# ProPrj_ZXD-BLE-Core_2025-01-08.net
KiCad netlist of a schematic drawn in EasyEDA Pro
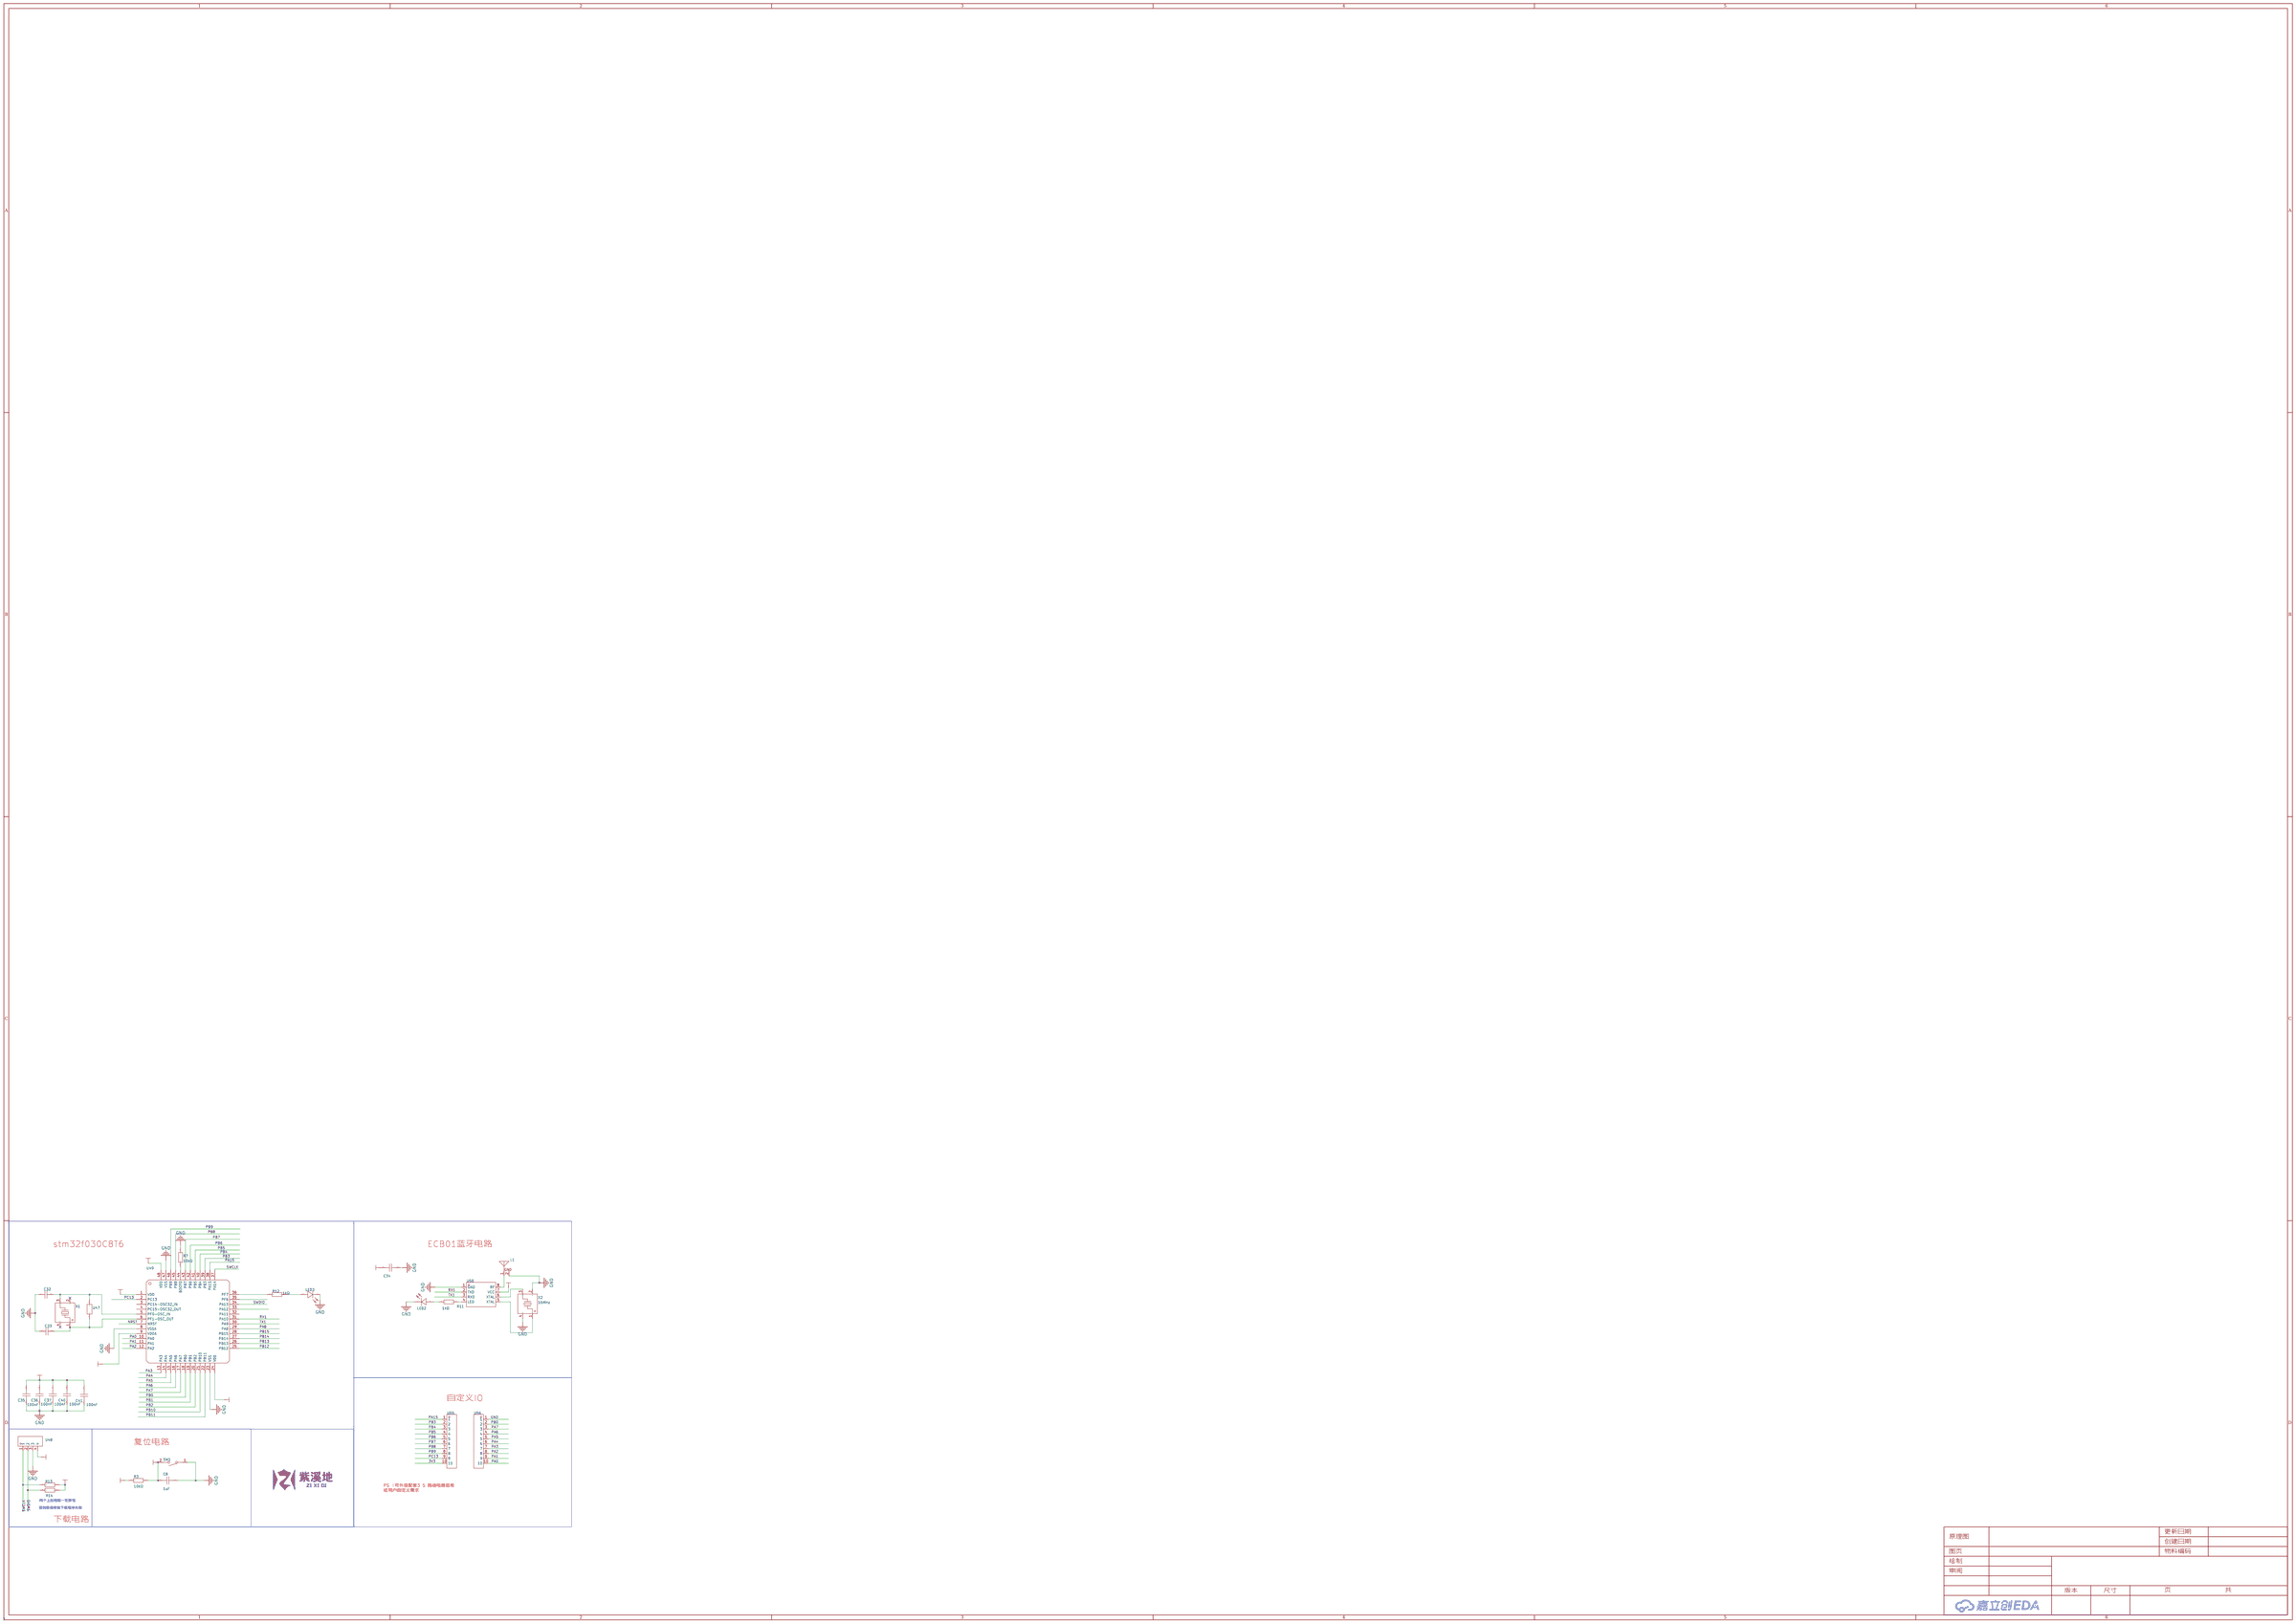
[diagram p0: schematic sheet]

(export (version "E")
  (design (tool "Eeschema 10.0.6"))
  (components
    (comp (ref "C8")
      (value "1uF")
      (fields
        (field (name "Manufacturer Part") "CL10A105KB8NNNC")
        (field (name "Manufacturer") "SAMSUNG(三星)")
      )
      (libsource (lib "easyedapro") (part "CC0603MRX5R8BB106"))
    )
    (comp (ref "C32")
      (value "22pF")
      (footprint "easyedapro:C0603")
      (description "容值:22pF;精度:±5%;额定电压:50V;材质(温度系数):C0G;")
      (fields
        (field (name "Manufacturer Part") "CL10C220JB8NNNC")
        (field (name "Manufacturer") "SAMSUNG(三星)")
      )
      (libsource (lib "easyedapro") (part "CL10C220JB8NNNC"))
    )
    (comp (ref "C33")
      (value "22pF")
      (footprint "easyedapro:C0603")
      (description "容值:22pF;精度:±5%;额定电压:50V;材质(温度系数):C0G;")
      (fields
        (field (name "Manufacturer Part") "CL10C220JB8NNNC")
        (field (name "Manufacturer") "SAMSUNG(三星)")
      )
      (libsource (lib "easyedapro") (part "CL10C220JB8NNNC"))
    )
    (comp (ref "C34")
      (value "100nF")
      (footprint "easyedapro:C0603")
      (description "容值:100nF;精度:±10%;额定电压:50V;材质(温度系数):X7R;")
      (fields
        (field (name "Manufacturer Part") "CGA0603X7R104K500JT")
        (field (name "Manufacturer") "HRE(芯声)")
      )
      (libsource (lib "easyedapro") (part "cga0603x7r104k500jt"))
    )
    (comp (ref "C35")
      (value "100nF")
      (footprint "easyedapro:C0603")
      (description "容值:100nF;精度:±10%;额定电压:50V;材质(温度系数):X7R;")
      (fields
        (field (name "Manufacturer Part") "CC0603KRX7R9BB104")
        (field (name "Manufacturer") "YAGEO(国巨)")
      )
      (libsource (lib "easyedapro") (part "CC0603KRX7R9BB104"))
    )
    (comp (ref "C36")
      (value "100nF")
      (footprint "easyedapro:C0603")
      (description "容值:100nF;精度:±10%;额定电压:50V;材质(温度系数):X7R;")
      (fields
        (field (name "Manufacturer Part") "CC0603KRX7R9BB104")
        (field (name "Manufacturer") "YAGEO(国巨)")
      )
      (libsource (lib "easyedapro") (part "CC0603KRX7R9BB104"))
    )
    (comp (ref "C37")
      (value "100nF")
      (footprint "easyedapro:C0603")
      (description "容值:100nF;精度:±10%;额定电压:50V;材质(温度系数):X7R;")
      (fields
        (field (name "Manufacturer Part") "CC0603KRX7R9BB104")
        (field (name "Manufacturer") "YAGEO(国巨)")
      )
      (libsource (lib "easyedapro") (part "CC0603KRX7R9BB104"))
    )
    (comp (ref "C40")
      (value "100nF")
      (footprint "easyedapro:C0603")
      (description "容值:100nF;精度:±10%;额定电压:50V;材质(温度系数):X7R;")
      (fields
        (field (name "Manufacturer Part") "CC0603KRX7R9BB104")
        (field (name "Manufacturer") "YAGEO(国巨)")
      )
      (libsource (lib "easyedapro") (part "CC0603KRX7R9BB104"))
    )
    (comp (ref "C41")
      (value "100nF")
      (footprint "easyedapro:C0603")
      (description "容值:100nF;精度:±10%;额定电压:50V;材质(温度系数):X7R;")
      (fields
        (field (name "Manufacturer Part") "CC0603KRX7R9BB104")
        (field (name "Manufacturer") "YAGEO(国巨)")
      )
      (libsource (lib "easyedapro") (part "CC0603KRX7R9BB104"))
    )
    (comp (ref "L1")
      (value "2.4G-ANT")
      (footprint "easyedapro:2.4G-ANT")
      (fields (field (name "Manufacturer Part") "KH3216-A55") (field (name "Manufacturer") "kinghelm(金航标)"))
      (libsource (lib "easyedapro") (part "2.4G-ANT"))
    )
    (comp (ref "LED2")
      (value "KT-0603R")
      (footprint "easyedapro:LED0603-RD")
      (description "发光颜色:红色;功率:-;正向电流:-;主波长:-;二极管配置:-;透镜颜色:-;色温:-;发光角度:-;载带方式:-;工作温度:-40°C~+85°C;")
      (fields (field (name "Manufacturer") "KENTO"))
      (libsource (lib "easyedapro") (part "KT-0603R"))
    )
    (comp (ref "LED3")
      (value "XL-1608UBC-04")
      (footprint "easyedapro:LED0603-RD_BLUE")
      (description "发光颜色:蓝色;功率:80mW;正向电流:25mA;主波长:460nm~469nm;透镜颜色:无色透明透镜;色温:-;发光角度:120°;载带方式:正贴;工作温度:-30°C~+85°C;")
      (fields (field (name "Manufacturer") "XINGLIGHT(成兴光)"))
      (libsource (lib "easyedapro") (part "XL-1608UBC-04"))
    )
    (comp (ref "R3")
      (value "10kΩ")
      (footprint "easyedapro:R0603")
      (description "电阻类型:厚膜电阻;阻值:10kΩ;精度:±1%;功率:100mW;最大工作电压:75V;温度系数:±100ppm/°C;")
      (fields
        (field (name "Manufacturer Part") "0603WAF1002T5E")
        (field (name "Manufacturer") "UNI-ROYAL(厚声)")
      )
      (libsource (lib "easyedapro") (part "0603WAF1002T5E"))
    )
    (comp (ref "R7")
      (value "10kΩ")
      (footprint "easyedapro:R0603")
      (description "电阻类型:厚膜电阻;阻值:10kΩ;精度:±1%;功率:100mW;最大工作电压:75V;温度系数:±100ppm/°C;")
      (fields
        (field (name "Manufacturer Part") "0603WAF1002T5E")
        (field (name "Manufacturer") "UNI-ROYAL(厚声)")
      )
      (libsource (lib "easyedapro") (part "0603WAF1002T5E"))
    )
    (comp (ref "R11")
      (value "1kΩ")
      (footprint "easyedapro:R0603")
      (description "电阻类型:厚膜电阻;阻值:1kΩ;精度:±1%;功率:100mW;最大工作电压:75V;温度系数:±100ppm/°C;")
      (fields
        (field (name "Manufacturer Part") "0603WAF1001T5E")
        (field (name "Manufacturer") "UNI-ROYAL(厚声)")
      )
      (libsource (lib "easyedapro") (part "0603WAF1001T5E"))
    )
    (comp (ref "R12")
      (value "1kΩ")
      (footprint "easyedapro:R0603")
      (description "电阻类型:厚膜电阻;阻值:1kΩ;精度:±1%;功率:100mW;最大工作电压:75V;温度系数:±100ppm/°C;")
      (fields
        (field (name "Manufacturer Part") "0603WAF1001T5E")
        (field (name "Manufacturer") "UNI-ROYAL(厚声)")
      )
      (libsource (lib "easyedapro") (part "0603WAF1001T5E"))
    )
    (comp (ref "R13")
      (value "10kΩ")
      (footprint "easyedapro:R0603")
      (description "电阻类型:厚膜电阻;阻值:10kΩ;精度:±1%;功率:100mW;最大工作电压:75V;温度系数:±100ppm/°C;")
      (fields
        (field (name "Manufacturer Part") "0603WAF1002T5E")
        (field (name "Manufacturer") "UNI-ROYAL(厚声)")
      )
      (libsource (lib "easyedapro") (part "0603WAF1002T5E"))
    )
    (comp (ref "R14")
      (value "10kΩ")
      (footprint "easyedapro:R0603")
      (description "电阻类型:厚膜电阻;阻值:10kΩ;精度:±1%;功率:100mW;最大工作电压:75V;温度系数:±100ppm/°C;")
      (fields
        (field (name "Manufacturer Part") "0603WAF1002T5E")
        (field (name "Manufacturer") "UNI-ROYAL(厚声)")
      )
      (libsource (lib "easyedapro") (part "0603WAF1002T5E"))
    )
    (comp (ref "SW1")
      (value "轻触按键3*4*H")
      (footprint "easyedapro:SW-SMD_L4.0-W2.9-LS5.0")
      (libsource (lib "easyedapro") (part "轻触按键3*4*H"))
    )
    (comp (ref "U47")
      (value "1mΩ")
      (footprint "easyedapro:R0603")
      (description "电阻类型:-;阻值:1mΩ;精度:±1%;功率:100mW;温度系数:±300ppm/°C;")
      (fields
        (field (name "Manufacturer Part") "PA0603FRP070R001L")
        (field (name "Manufacturer") "YAGEO(国巨)")
      )
      (libsource (lib "easyedapro") (part "PA0603FRP070R001L"))
    )
    (comp (ref "U48")
      (value "XH2.54_4P_直插")
      (footprint "easyedapro:CONN-TH_4P-P2.50-XH2.54-4P")
      (libsource (lib "easyedapro") (part "XH2.54_4P_直插"))
    )
    (comp (ref "U49")
      (value "STM32F030C8T6TR")
      (footprint "easyedapro:LQFP-48_L7.0-W7.0-P0.50-LS9.0-BL")
      (description "CPU内核:ARM-M0;程序存储容量:64KB;RAM总容量:8KB;GPIO端口数量:39;工作电压范围:2.4V~3.6V;CPU最大主频:48MHz;程序存储器类型:FLASH;")
      (fields (field (name "Manufacturer") "ST(意法半导体)"))
      (libsource (lib "easyedapro") (part "stm32f030c8t6tr"))
    )
    (comp (ref "U50")
      (value "ECB01C")
      (footprint "easyedapro:SOP-8_L4.9-W3.9-P1.27-LS6.0-BL")
      (libsource (lib "easyedapro") (part "ECB01C"))
    )
    (comp (ref "U55")
      (value "HDGCPH-PZ01-10")
      (footprint "easyedapro:HDR-TH_10P-P2.54-V-M_1")
      (fields (field (name "Manufacturer") "HDGC(华德共创)"))
      (libsource (lib "easyedapro") (part "HDGCPH-PZ01-10"))
    )
    (comp (ref "U56")
      (value "HDGCPH-PZ01-10")
      (footprint "easyedapro:HDR-TH_10P-P2.54-V-M_1")
      (fields (field (name "Manufacturer") "HDGC(华德共创)"))
      (libsource (lib "easyedapro") (part "HDGCPH-PZ01-10"))
    )
    (comp (ref "X1")
      (value "8MHz")
      (footprint "easyedapro:OSC-SMD_4P-L3.2-W2.5-BL")
      (description "晶振类型:贴片晶振;频率:8MHz;常温频差:±10ppm;外接负载电容:12pF;频率稳定度(全温):±20ppm;")
      (fields (field (name "Manufacturer Part") "X32258MOB4SI") (field (name "Manufacturer") "YXC(扬兴晶振)"))
      (libsource (lib "easyedapro") (part "x32258mob4si"))
    )
    (comp (ref "X2")
      (value "16MHz")
      (footprint "easyedapro:CRYSTAL-SMD_4P-L3.2-W2.5-BL-1")
      (description "频率:16MHz;常温频差:±20ppm;外接负载电容:8pF;频率稳定度(全温):±50ppm;")
      (fields
        (field (name "Manufacturer Part") "ABM8AIG-16.000MHZ-82Z-T")
        (field (name "Manufacturer") "ABRACON")
      )
      (libsource (lib "easyedapro") (part "ABM8AIG-16.000MHZ-82Z-T"))
    )
  )
  (nets
    (net (code "1") (name "/PA0") (class "Default")
      (node (ref "U49") (pin "10") (pinfunction "PA0_10") (pintype "unspecified"))
      (node (ref "U56") (pin "10") (pinfunction "10_10") (pintype "unspecified"))
    )
    (net (code "2") (name "/PA1") (class "Default")
      (node (ref "U49") (pin "11") (pinfunction "PA1_11") (pintype "unspecified"))
      (node (ref "U56") (pin "9") (pinfunction "9_9") (pintype "unspecified"))
    )
    (net (code "3") (name "/PA2") (class "Default")
      (node (ref "U49") (pin "12") (pinfunction "PA2_12") (pintype "unspecified"))
      (node (ref "U56") (pin "8") (pinfunction "8_8") (pintype "unspecified"))
    )
    (net (code "4") (name "/PA3") (class "Default")
      (node (ref "U49") (pin "13") (pinfunction "PA3_13") (pintype "unspecified"))
      (node (ref "U56") (pin "7") (pinfunction "7_7") (pintype "unspecified"))
    )
    (net (code "5") (name "/PA4") (class "Default")
      (node (ref "U49") (pin "14") (pinfunction "PA4_14") (pintype "unspecified"))
      (node (ref "U56") (pin "6") (pinfunction "6_6") (pintype "unspecified"))
    )
    (net (code "6") (name "/PA5") (class "Default")
      (node (ref "U49") (pin "15") (pinfunction "PA5_15") (pintype "unspecified"))
      (node (ref "U56") (pin "5") (pinfunction "5_5") (pintype "unspecified"))
    )
    (net (code "7") (name "/PA6") (class "Default")
      (node (ref "U49") (pin "16") (pinfunction "PA6_16") (pintype "unspecified"))
      (node (ref "U56") (pin "4") (pinfunction "4_4") (pintype "unspecified"))
    )
    (net (code "8") (name "/PA7") (class "Default")
      (node (ref "U49") (pin "17") (pinfunction "PA7_17") (pintype "unspecified"))
      (node (ref "U56") (pin "3") (pinfunction "3_3") (pintype "unspecified"))
    )
    (net (code "9") (name "/PA8") (class "Default")
      (node (ref "U49") (pin "29") (pinfunction "PA8_29") (pintype "unspecified"))
    )
    (net (code "10") (name "/PA15") (class "Default")
      (node (ref "U49") (pin "38") (pinfunction "PA15_38") (pintype "unspecified"))
      (node (ref "U55") (pin "1") (pinfunction "1_1") (pintype "unspecified"))
    )
    (net (code "11") (name "/PB0") (class "Default")
      (node (ref "U49") (pin "18") (pinfunction "PB0_18") (pintype "unspecified"))
      (node (ref "U56") (pin "2") (pinfunction "2_2") (pintype "unspecified"))
    )
    (net (code "12") (name "/PB1") (class "Default")
      (node (ref "U49") (pin "19") (pinfunction "PB1_19") (pintype "unspecified"))
    )
    (net (code "13") (name "/PB2") (class "Default")
      (node (ref "U49") (pin "20") (pinfunction "PB2_20") (pintype "unspecified"))
    )
    (net (code "14") (name "/PB3") (class "Default")
      (node (ref "U49") (pin "39") (pinfunction "PB3_39") (pintype "unspecified"))
      (node (ref "U55") (pin "2") (pinfunction "2_2") (pintype "unspecified"))
    )
    (net (code "15") (name "/PB4") (class "Default")
      (node (ref "U49") (pin "40") (pinfunction "PB4_40") (pintype "unspecified"))
      (node (ref "U55") (pin "3") (pinfunction "3_3") (pintype "unspecified"))
    )
    (net (code "16") (name "/PB5") (class "Default")
      (node (ref "U49") (pin "41") (pinfunction "PB5_41") (pintype "unspecified"))
      (node (ref "U55") (pin "4") (pinfunction "4_4") (pintype "unspecified"))
    )
    (net (code "17") (name "/PB6") (class "Default")
      (node (ref "U49") (pin "42") (pinfunction "PB6_42") (pintype "unspecified"))
      (node (ref "U55") (pin "5") (pinfunction "5_5") (pintype "unspecified"))
    )
    (net (code "18") (name "/PB7") (class "Default")
      (node (ref "U49") (pin "43") (pinfunction "PB7_43") (pintype "unspecified"))
      (node (ref "U55") (pin "6") (pinfunction "6_6") (pintype "unspecified"))
    )
    (net (code "19") (name "/PB8") (class "Default")
      (node (ref "U49") (pin "45") (pinfunction "PB8_45") (pintype "unspecified"))
      (node (ref "U55") (pin "7") (pinfunction "7_7") (pintype "unspecified"))
    )
    (net (code "20") (name "/PB9") (class "Default")
      (node (ref "U49") (pin "46") (pinfunction "PB9_46") (pintype "unspecified"))
      (node (ref "U55") (pin "8") (pinfunction "8_8") (pintype "unspecified"))
    )
    (net (code "21") (name "/PB10") (class "Default")
      (node (ref "U49") (pin "21") (pinfunction "PB10_21") (pintype "unspecified"))
    )
    (net (code "22") (name "/PB11") (class "Default")
      (node (ref "U49") (pin "22") (pinfunction "PB11_22") (pintype "unspecified"))
    )
    (net (code "23") (name "/PB12") (class "Default")
      (node (ref "U49") (pin "25") (pinfunction "PB12_25") (pintype "unspecified"))
    )
    (net (code "24") (name "/PB13") (class "Default")
      (node (ref "U49") (pin "26") (pinfunction "PB13_26") (pintype "unspecified"))
    )
    (net (code "25") (name "/PB14") (class "Default")
      (node (ref "U49") (pin "27") (pinfunction "PB14_27") (pintype "unspecified"))
    )
    (net (code "26") (name "/PB15") (class "Default")
      (node (ref "U49") (pin "28") (pinfunction "PB15_28") (pintype "unspecified"))
    )
    (net (code "27") (name "/PC13") (class "Default")
      (node (ref "U49") (pin "2") (pinfunction "PC13_2") (pintype "unspecified"))
      (node (ref "U55") (pin "9") (pinfunction "9_9") (pintype "unspecified"))
    )
    (net (code "28") (name "/RX1") (class "Default")
      (node (ref "U49") (pin "31") (pinfunction "PA10_31") (pintype "unspecified"))
      (node (ref "U50") (pin "2") (pinfunction "TXD_2") (pintype "unspecified"))
    )
    (net (code "29") (name "/SWCLK") (class "Default")
      (node (ref "R13") (pin "1") (pinfunction "1_1") (pintype "input"))
      (node (ref "U48") (pin "1") (pinfunction "1_1") (pintype "unspecified"))
      (node (ref "U49") (pin "37") (pinfunction "PA14_37") (pintype "unspecified"))
    )
    (net (code "30") (name "/SWDIO") (class "Default")
      (node (ref "R14") (pin "1") (pinfunction "1_1") (pintype "input"))
      (node (ref "U48") (pin "2") (pinfunction "2_2") (pintype "unspecified"))
      (node (ref "U49") (pin "34") (pinfunction "PA13_34") (pintype "unspecified"))
    )
    (net (code "31") (name "/TX1") (class "Default")
      (node (ref "U49") (pin "30") (pinfunction "PA9_30") (pintype "unspecified"))
      (node (ref "U50") (pin "3") (pinfunction "RXD_3") (pintype "unspecified"))
    )
    (net (code "32") (name "3V3") (class "Default")
      (node (ref "C34") (pin "2") (pinfunction "2_2") (pintype "unspecified"))
      (node (ref "C35") (pin "2") (pinfunction "2_2") (pintype "input"))
      (node (ref "C36") (pin "2") (pinfunction "2_2") (pintype "input"))
      (node (ref "C37") (pin "2") (pinfunction "2_2") (pintype "input"))
      (node (ref "C40") (pin "2") (pinfunction "2_2") (pintype "input"))
      (node (ref "C41") (pin "2") (pinfunction "2_2") (pintype "input"))
      (node (ref "R13") (pin "2") (pinfunction "2_2") (pintype "input"))
      (node (ref "R14") (pin "2") (pinfunction "2_2") (pintype "input"))
      (node (ref "R3") (pin "2") (pinfunction "2_2") (pintype "input"))
      (node (ref "U48") (pin "4") (pinfunction "4_4") (pintype "unspecified"))
      (node (ref "U49") (pin "1") (pinfunction "VDD_1") (pintype "unspecified"))
      (node (ref "U49") (pin "24") (pinfunction "VDD_24") (pintype "unspecified"))
      (node (ref "U49") (pin "48") (pinfunction "VDD_48") (pintype "unspecified"))
      (node (ref "U49") (pin "9") (pinfunction "VDDA_9") (pintype "unspecified"))
      (node (ref "U50") (pin "7") (pinfunction "VCC_7") (pintype "unspecified"))
      (node (ref "U55") (pin "10") (pinfunction "10_10") (pintype "unspecified"))
    )
    (net (code "33") (name "GND") (class "Default")
      (node (ref "C32") (pin "1") (pinfunction "1_1") (pintype "input"))
      (node (ref "C33") (pin "1") (pinfunction "1_1") (pintype "input"))
      (node (ref "C34") (pin "1") (pinfunction "1_1") (pintype "unspecified"))
      (node (ref "C35") (pin "1") (pinfunction "1_1") (pintype "input"))
      (node (ref "C36") (pin "1") (pinfunction "1_1") (pintype "input"))
      (node (ref "C37") (pin "1") (pinfunction "1_1") (pintype "input"))
      (node (ref "C40") (pin "1") (pinfunction "1_1") (pintype "input"))
      (node (ref "C41") (pin "1") (pinfunction "1_1") (pintype "input"))
      (node (ref "C8") (pin "1") (pinfunction "1_1") (pintype "input"))
      (node (ref "L1") (pin "2") (pinfunction "NC_2") (pintype "input"))
      (node (ref "LED2") (pin "1") (pinfunction "K_1") (pintype "unspecified"))
      (node (ref "LED3") (pin "1") (pinfunction "K_1") (pintype "unspecified"))
      (node (ref "R7") (pin "2") (pinfunction "2_2") (pintype "input"))
      (node (ref "SW1") (pin "1") (pinfunction "1_1") (pintype "unspecified"))
      (node (ref "U48") (pin "3") (pinfunction "3_3") (pintype "unspecified"))
      (node (ref "U49") (pin "23") (pinfunction "VSS_23") (pintype "unspecified"))
      (node (ref "U49") (pin "47") (pinfunction "VSS_47") (pintype "unspecified"))
      (node (ref "U49") (pin "8") (pinfunction "VSSA_8") (pintype "unspecified"))
      (node (ref "U50") (pin "1") (pinfunction "GND_1") (pintype "unspecified"))
      (node (ref "U56") (pin "1") (pinfunction "1_1") (pintype "unspecified"))
      (node (ref "X2") (pin "2") (pinfunction "GND_2") (pintype "input"))
      (node (ref "X2") (pin "4") (pinfunction "GND_4") (pintype "input"))
    )
    (net (code "34") (name "NRST") (class "Default")
      (node (ref "C8") (pin "2") (pinfunction "2_2") (pintype "input"))
      (node (ref "R3") (pin "1") (pinfunction "1_1") (pintype "input"))
      (node (ref "SW1") (pin "2") (pinfunction "2_2") (pintype "unspecified"))
      (node (ref "U49") (pin "7") (pinfunction "NRST_7") (pintype "unspecified"))
    )
    (net (code "35") (name "Net-(LED2-A)") (class "Default")
      (node (ref "LED2") (pin "2") (pinfunction "A_2") (pintype "unspecified"))
      (node (ref "R11") (pin "1") (pinfunction "1_1") (pintype "input"))
    )
    (net (code "36") (name "Net-(LED3-A)") (class "Default")
      (node (ref "LED3") (pin "2") (pinfunction "A_2") (pintype "unspecified"))
      (node (ref "R12") (pin "2") (pinfunction "2_2") (pintype "input"))
    )
    (net (code "37") (name "Net-(U49-BOOT0)") (class "Default")
      (node (ref "R7") (pin "1") (pinfunction "1_1") (pintype "input"))
      (node (ref "U49") (pin "44") (pinfunction "BOOT0_44") (pintype "unspecified"))
    )
    (net (code "38") (name "Net-(U49-PF0-OSC_IN)") (class "Default")
      (node (ref "C32") (pin "2") (pinfunction "2_2") (pintype "input"))
      (node (ref "U47") (pin "2") (pinfunction "2_2") (pintype "unspecified"))
      (node (ref "U49") (pin "5") (pinfunction "PF0-OSC_IN_5") (pintype "unspecified"))
      (node (ref "X1") (pin "3") (pinfunction "3_3") (pintype "input"))
    )
    (net (code "39") (name "Net-(U49-PF1-OSC_OUT)") (class "Default")
      (node (ref "C33") (pin "2") (pinfunction "2_2") (pintype "input"))
      (node (ref "U47") (pin "1") (pinfunction "1_1") (pintype "unspecified"))
      (node (ref "U49") (pin "6") (pinfunction "PF1-OSC_OUT_6") (pintype "unspecified"))
      (node (ref "X1") (pin "1") (pinfunction "1_1") (pintype "input"))
    )
    (net (code "40") (name "Net-(U49-PF7)") (class "Default")
      (node (ref "R12") (pin "1") (pinfunction "1_1") (pintype "input"))
      (node (ref "U49") (pin "36") (pinfunction "PF7_36") (pintype "unspecified"))
    )
    (net (code "41") (name "Net-(U50-LED)") (class "Default")
      (node (ref "R11") (pin "2") (pinfunction "2_2") (pintype "input"))
      (node (ref "U50") (pin "4") (pinfunction "LED_4") (pintype "unspecified"))
    )
    (net (code "42") (name "Net-(U50-RF)") (class "Default")
      (node (ref "L1") (pin "1") (pinfunction "1_1") (pintype "input"))
      (node (ref "U50") (pin "8") (pinfunction "RF_8") (pintype "unspecified"))
    )
    (net (code "43") (name "Net-(U50-XTAL-Pad5)") (class "Default")
      (node (ref "U50") (pin "5") (pinfunction "XTAL_5") (pintype "unspecified"))
      (node (ref "X2") (pin "1") (pinfunction "1_1") (pintype "input"))
    )
    (net (code "44") (name "Net-(U50-XTAL-Pad6)") (class "Default")
      (node (ref "U50") (pin "6") (pinfunction "XTAL_6") (pintype "unspecified"))
      (node (ref "X2") (pin "3") (pinfunction "3_3") (pintype "input"))
    )
    (net (code "45") (name "unconnected-(U49-PA11-Pad32)") (class "Default")
      (node (ref "U49") (pin "32") (pinfunction "PA11_32") (pintype "unspecified"))
    )
    (net (code "46") (name "unconnected-(U49-PA12-Pad33)") (class "Default")
      (node (ref "U49") (pin "33") (pinfunction "PA12_33") (pintype "unspecified"))
    )
    (net (code "47") (name "unconnected-(U49-PC14-OSC32_IN-Pad3)") (class "Default")
      (node (ref "U49") (pin "3") (pinfunction "PC14-OSC32_IN_3") (pintype "unspecified"))
    )
    (net (code "48") (name "unconnected-(U49-PC15-OSC32_OUT-Pad4)") (class "Default")
      (node (ref "U49") (pin "4") (pinfunction "PC15-OSC32_OUT_4") (pintype "unspecified"))
    )
    (net (code "49") (name "unconnected-(U49-PF6-Pad35)") (class "Default")
      (node (ref "U49") (pin "35") (pinfunction "PF6_35") (pintype "unspecified"))
    )
    (net (code "50") (name "unconnected-(X1-GND-Pad2)") (class "Default")
      (node (ref "X1") (pin "2") (pinfunction "GND_2") (pintype "input+no_connect"))
    )
    (net (code "51") (name "unconnected-(X1-GND-Pad4)") (class "Default")
      (node (ref "X1") (pin "4") (pinfunction "GND_4") (pintype "input+no_connect"))
    )
  )
)
